# Intelligent_Agriculture_Wifi.net
KiCad netlist of a schematic drawn in Altium Designer
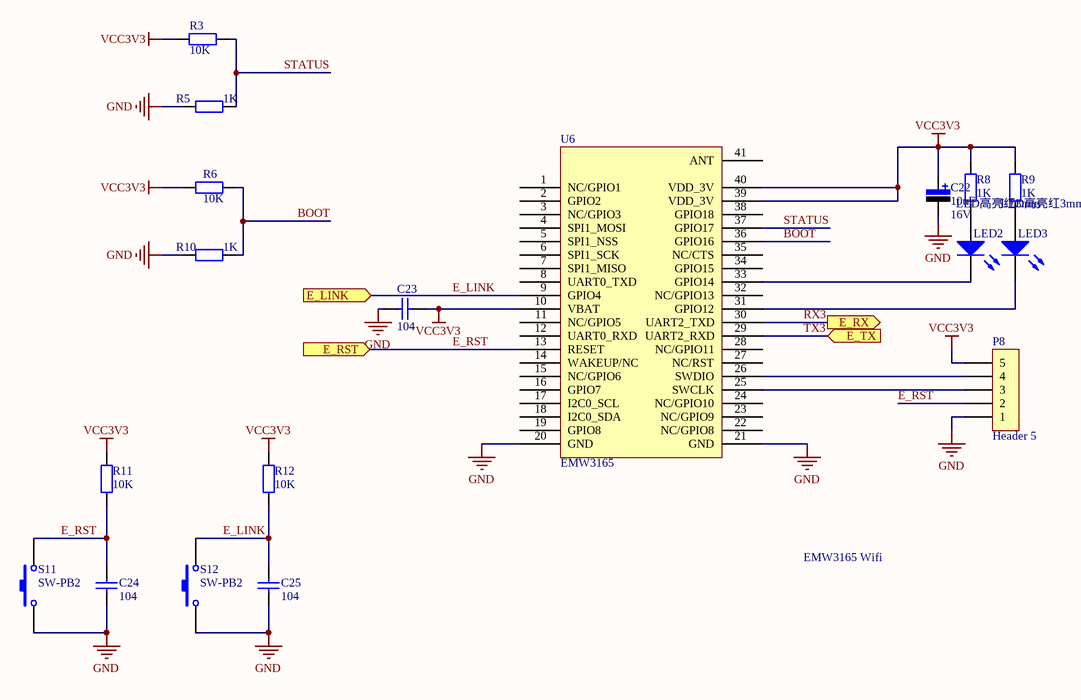
[diagram p0: Intelligent_Agriculture_Wifi.SchDoc]

(export (version "E")
  (design (tool "Eeschema 10.0.6"))
  (components
    (comp (ref "C22")
      (value "10uF")
      (footprint "CAP-3528")
      (description "钽电容")
      (fields
        (field (name "VOL") "16V")
        (field (name "Comment") "Cap Pol")
        (field (name "PUBLISHER") "Altium Limited")
      )
      (libsource (lib "Intelligent_Agriculture_Lib") (part "Cap Pol"))
    )
    (comp (ref "C23")
      (value "104")
      (footprint "C-RAD-0805")
      (description "无极性电容")
      (fields (field (name "Comment") "Cap") (field (name "PUBLISHER") "Altium Limited"))
      (libsource (lib "Intelligent_Agriculture_Lib") (part "Cap"))
    )
    (comp (ref "C24")
      (value "104")
      (footprint "C-RAD-0805")
      (description "无极性电容")
      (fields (field (name "Comment") "Cap") (field (name "PUBLISHER") "Altium Limited"))
      (libsource (lib "Intelligent_Agriculture_Lib") (part "Cap"))
    )
    (comp (ref "C25")
      (value "104")
      (footprint "C-RAD-0805")
      (description "无极性电容")
      (fields (field (name "Comment") "Cap") (field (name "PUBLISHER") "Altium Limited"))
      (libsource (lib "Intelligent_Agriculture_Lib") (part "Cap"))
    )
    (comp (ref "LED2")
      (value "LED0")
      (footprint "LED_A2")
      (description "发光二极管")
      (fields (field (name "PUBLISHER") "Altium Limited"))
      (libsource (lib "Intelligent_Agriculture_Lib") (part "LED0"))
    )
    (comp (ref "LED3")
      (value "LED0")
      (footprint "LED_A2")
      (description "发光二极管")
      (fields (field (name "PUBLISHER") "Altium Limited"))
      (libsource (lib "Intelligent_Agriculture_Lib") (part "LED0"))
    )
    (comp (ref "P8")
      (value "Header 5")
      (footprint "HDR5_A1")
      (description "接插件")
      (fields (field (name "PUBLISHER") "Altium Limited"))
      (libsource (lib "fszhang") (part "Header 5"))
    )
    (comp (ref "R3")
      (value "10K")
      (description "贴片电阻")
      (fields (field (name "Comment") "Res1") (field (name "PUBLISHER") "Altium Limited"))
      (libsource (lib "") (part "Res1_1"))
    )
    (comp (ref "R5")
      (value "1K")
      (description "贴片电阻")
      (fields (field (name "Comment") "Res1") (field (name "PUBLISHER") "Altium Limited"))
      (libsource (lib "") (part "Res1_1"))
    )
    (comp (ref "R6")
      (value "10K")
      (description "贴片电阻")
      (fields (field (name "Comment") "Res1") (field (name "PUBLISHER") "Altium Limited"))
      (libsource (lib "") (part "Res1_1"))
    )
    (comp (ref "R8")
      (value "1K")
      (description "贴片电阻")
      (fields (field (name "Comment") "Res1") (field (name "PUBLISHER") "Altium Limited"))
      (libsource (lib "fszhang") (part "Res1"))
    )
    (comp (ref "R9")
      (value "1K")
      (description "贴片电阻")
      (fields (field (name "Comment") "Res1") (field (name "PUBLISHER") "Altium Limited"))
      (libsource (lib "fszhang") (part "Res1"))
    )
    (comp (ref "R10")
      (value "1K")
      (description "贴片电阻")
      (fields (field (name "Comment") "Res1") (field (name "PUBLISHER") "Altium Limited"))
      (libsource (lib "") (part "Res1_1"))
    )
    (comp (ref "R11")
      (value "10K")
      (description "贴片电阻")
      (fields (field (name "Comment") "Res1") (field (name "PUBLISHER") "Altium Limited"))
      (libsource (lib "") (part "Res1_2"))
    )
    (comp (ref "R12")
      (value "10K")
      (description "贴片电阻")
      (fields (field (name "Comment") "Res1") (field (name "PUBLISHER") "Altium Limited"))
      (libsource (lib "fszhang") (part "Res1"))
    )
    (comp (ref "S11")
      (value "SW-PB2")
      (footprint "SW_PB2-S-3*6*2.5")
      (description "微动开关")
      (fields (field (name "PUBLISHER") "Altium Limited"))
      (libsource (lib "Intelligent_Agriculture_Lib") (part "SW-PB2"))
    )
    (comp (ref "S12")
      (value "SW-PB2")
      (footprint "SW_PB2-S-3*6*2.5")
      (description "微动开关")
      (fields (field (name "PUBLISHER") "Altium Limited"))
      (libsource (lib "Intelligent_Agriculture_Lib") (part "SW-PB2"))
    )
    (comp (ref "U6")
      (value "EMW3165")
      (footprint "EMW3165")
      (description "WIFI 模块")
      (libsource (lib "Intelligent_Agriculture") (part "EMW3165"))
    )
  )
  (nets
    (net (code "1") (name "/BOOT") (class "Default")
      (node (ref "R10") (pin "1") (pinfunction "1_1") (pintype "passive"))
      (node (ref "R6") (pin "1") (pinfunction "1_1") (pintype "passive"))
      (node (ref "U6") (pin "36") (pinfunction "GPIO16_36") (pintype "passive"))
    )
    (net (code "2") (name "/E_LINK") (class "Default")
      (node (ref "C25") (pin "1") (pinfunction "1_1") (pintype "passive"))
      (node (ref "R12") (pin "1") (pinfunction "1_1") (pintype "passive"))
      (node (ref "S12") (pin "2") (pinfunction "2_2") (pintype "passive"))
      (node (ref "U6") (pin "9") (pinfunction "GPIO4_9") (pintype "passive"))
    )
    (net (code "3") (name "/E_RST") (class "Default")
      (node (ref "C24") (pin "1") (pinfunction "1_1") (pintype "passive"))
      (node (ref "P8") (pin "2") (pinfunction "2_2") (pintype "passive"))
      (node (ref "R11") (pin "2") (pinfunction "2_2") (pintype "passive"))
      (node (ref "S11") (pin "2") (pinfunction "2_2") (pintype "passive"))
      (node (ref "U6") (pin "13") (pinfunction "RESET_13") (pintype "passive"))
    )
    (net (code "4") (name "/RX3") (class "Default")
      (node (ref "U6") (pin "30") (pinfunction "UART2_TXD_30") (pintype "passive"))
    )
    (net (code "5") (name "/STATUS") (class "Default")
      (node (ref "R3") (pin "1") (pinfunction "1_1") (pintype "passive"))
      (node (ref "R5") (pin "1") (pinfunction "1_1") (pintype "passive"))
      (node (ref "U6") (pin "37") (pinfunction "GPIO17_37") (pintype "passive"))
    )
    (net (code "6") (name "/TX3") (class "Default")
      (node (ref "U6") (pin "29") (pinfunction "UART2_RXD_29") (pintype "passive"))
    )
    (net (code "7") (name "GND") (class "Default")
      (node (ref "C22") (pin "2") (pinfunction "2_2") (pintype "passive"))
      (node (ref "C23") (pin "1") (pinfunction "1_1") (pintype "passive"))
      (node (ref "C24") (pin "2") (pinfunction "2_2") (pintype "passive"))
      (node (ref "C25") (pin "2") (pinfunction "2_2") (pintype "passive"))
      (node (ref "P8") (pin "1") (pinfunction "1_1") (pintype "passive"))
      (node (ref "R10") (pin "2") (pinfunction "2_2") (pintype "passive"))
      (node (ref "R5") (pin "2") (pinfunction "2_2") (pintype "passive"))
      (node (ref "S11") (pin "1") (pinfunction "1_1") (pintype "passive"))
      (node (ref "S12") (pin "1") (pinfunction "1_1") (pintype "passive"))
      (node (ref "U6") (pin "20") (pinfunction "GND_20") (pintype "passive"))
      (node (ref "U6") (pin "21") (pinfunction "GND_21") (pintype "passive"))
    )
    (net (code "8") (name "Net-(LED2-A)") (class "Default")
      (node (ref "LED2") (pin "1") (pinfunction "A_1") (pintype "passive"))
      (node (ref "R8") (pin "1") (pinfunction "1_1") (pintype "passive"))
    )
    (net (code "9") (name "Net-(LED2-K)") (class "Default")
      (node (ref "LED2") (pin "2") (pinfunction "K_2") (pintype "passive"))
      (node (ref "U6") (pin "33") (pinfunction "GPIO14_33") (pintype "passive"))
    )
    (net (code "10") (name "Net-(LED3-A)") (class "Default")
      (node (ref "LED3") (pin "1") (pinfunction "A_1") (pintype "passive"))
      (node (ref "R9") (pin "1") (pinfunction "1_1") (pintype "passive"))
    )
    (net (code "11") (name "Net-(LED3-K)") (class "Default")
      (node (ref "LED3") (pin "2") (pinfunction "K_2") (pintype "passive"))
      (node (ref "U6") (pin "31") (pinfunction "GPIO12_31") (pintype "passive"))
    )
    (net (code "12") (name "Net-(U6-SWCLK)") (class "Default")
      (node (ref "P8") (pin "3") (pinfunction "3_3") (pintype "passive"))
      (node (ref "U6") (pin "25") (pinfunction "SWCLK_25") (pintype "passive"))
    )
    (net (code "13") (name "Net-(U6-SWDIO)") (class "Default")
      (node (ref "P8") (pin "4") (pinfunction "4_4") (pintype "passive"))
      (node (ref "U6") (pin "26") (pinfunction "SWDIO_26") (pintype "passive"))
    )
    (net (code "14") (name "VCC3V3") (class "Default")
      (node (ref "C22") (pin "1") (pinfunction "1_1") (pintype "passive"))
      (node (ref "C23") (pin "2") (pinfunction "2_2") (pintype "passive"))
      (node (ref "P8") (pin "5") (pinfunction "5_5") (pintype "passive"))
      (node (ref "R11") (pin "1") (pinfunction "1_1") (pintype "passive"))
      (node (ref "R12") (pin "2") (pinfunction "2_2") (pintype "passive"))
      (node (ref "R3") (pin "2") (pinfunction "2_2") (pintype "passive"))
      (node (ref "R6") (pin "2") (pinfunction "2_2") (pintype "passive"))
      (node (ref "R8") (pin "2") (pinfunction "2_2") (pintype "passive"))
      (node (ref "R9") (pin "2") (pinfunction "2_2") (pintype "passive"))
      (node (ref "U6") (pin "10") (pinfunction "VBAT_10") (pintype "passive"))
      (node (ref "U6") (pin "39") (pinfunction "VDD_3V_39") (pintype "passive"))
      (node (ref "U6") (pin "40") (pinfunction "VDD_3V_40") (pintype "passive"))
    )
    (net (code "15") (name "unconnected-(U6-ANT-Pad41)") (class "Default")
      (node (ref "U6") (pin "41") (pinfunction "ANT_41") (pintype "passive"))
    )
    (net (code "16") (name "unconnected-(U6-GPIO2-Pad2)") (class "Default")
      (node (ref "U6") (pin "2") (pinfunction "GPIO2_2") (pintype "passive"))
    )
    (net (code "17") (name "unconnected-(U6-GPIO7-Pad16)") (class "Default")
      (node (ref "U6") (pin "16") (pinfunction "GPIO7_16") (pintype "passive"))
    )
    (net (code "18") (name "unconnected-(U6-GPIO8-Pad19)") (class "Default")
      (node (ref "U6") (pin "19") (pinfunction "GPIO8_19") (pintype "passive"))
    )
    (net (code "19") (name "unconnected-(U6-GPIO15-Pad34)") (class "Default")
      (node (ref "U6") (pin "34") (pinfunction "GPIO15_34") (pintype "passive"))
    )
    (net (code "20") (name "unconnected-(U6-GPIO18-Pad38)") (class "Default")
      (node (ref "U6") (pin "38") (pinfunction "GPIO18_38") (pintype "passive"))
    )
    (net (code "21") (name "unconnected-(U6-I2C0_SCL-Pad17)") (class "Default")
      (node (ref "U6") (pin "17") (pinfunction "I2C0_SCL_17") (pintype "passive"))
    )
    (net (code "22") (name "unconnected-(U6-I2C0_SDA-Pad18)") (class "Default")
      (node (ref "U6") (pin "18") (pinfunction "I2C0_SDA_18") (pintype "passive"))
    )
    (net (code "23") (name "unconnected-(U6-NC{slash}CTS-Pad35)") (class "Default")
      (node (ref "U6") (pin "35") (pinfunction "NC/CTS_35") (pintype "passive"))
    )
    (net (code "24") (name "unconnected-(U6-NC{slash}GPIO1-Pad1)") (class "Default")
      (node (ref "U6") (pin "1") (pinfunction "NC/GPIO1_1") (pintype "passive"))
    )
    (net (code "25") (name "unconnected-(U6-NC{slash}GPIO3-Pad3)") (class "Default")
      (node (ref "U6") (pin "3") (pinfunction "NC/GPIO3_3") (pintype "passive"))
    )
    (net (code "26") (name "unconnected-(U6-NC{slash}GPIO5-Pad11)") (class "Default")
      (node (ref "U6") (pin "11") (pinfunction "NC/GPIO5_11") (pintype "passive"))
    )
    (net (code "27") (name "unconnected-(U6-NC{slash}GPIO6-Pad15)") (class "Default")
      (node (ref "U6") (pin "15") (pinfunction "NC/GPIO6_15") (pintype "passive"))
    )
    (net (code "28") (name "unconnected-(U6-NC{slash}GPIO8-Pad22)") (class "Default")
      (node (ref "U6") (pin "22") (pinfunction "NC/GPIO8_22") (pintype "passive"))
    )
    (net (code "29") (name "unconnected-(U6-NC{slash}GPIO9-Pad23)") (class "Default")
      (node (ref "U6") (pin "23") (pinfunction "NC/GPIO9_23") (pintype "passive"))
    )
    (net (code "30") (name "unconnected-(U6-NC{slash}GPIO10-Pad24)") (class "Default")
      (node (ref "U6") (pin "24") (pinfunction "NC/GPIO10_24") (pintype "passive"))
    )
    (net (code "31") (name "unconnected-(U6-NC{slash}GPIO11-Pad28)") (class "Default")
      (node (ref "U6") (pin "28") (pinfunction "NC/GPIO11_28") (pintype "passive"))
    )
    (net (code "32") (name "unconnected-(U6-NC{slash}GPIO13-Pad32)") (class "Default")
      (node (ref "U6") (pin "32") (pinfunction "NC/GPIO13_32") (pintype "passive"))
    )
    (net (code "33") (name "unconnected-(U6-NC{slash}RST-Pad27)") (class "Default")
      (node (ref "U6") (pin "27") (pinfunction "NC/RST_27") (pintype "passive"))
    )
    (net (code "34") (name "unconnected-(U6-SPI1_MISO-Pad7)") (class "Default")
      (node (ref "U6") (pin "7") (pinfunction "SPI1_MISO_7") (pintype "passive"))
    )
    (net (code "35") (name "unconnected-(U6-SPI1_MOSI-Pad4)") (class "Default")
      (node (ref "U6") (pin "4") (pinfunction "SPI1_MOSI_4") (pintype "passive"))
    )
    (net (code "36") (name "unconnected-(U6-SPI1_NSS-Pad5)") (class "Default")
      (node (ref "U6") (pin "5") (pinfunction "SPI1_NSS_5") (pintype "passive"))
    )
    (net (code "37") (name "unconnected-(U6-SPI1_SCK-Pad6)") (class "Default")
      (node (ref "U6") (pin "6") (pinfunction "SPI1_SCK_6") (pintype "passive"))
    )
    (net (code "38") (name "unconnected-(U6-UART0_RXD-Pad12)") (class "Default")
      (node (ref "U6") (pin "12") (pinfunction "UART0_RXD_12") (pintype "passive"))
    )
    (net (code "39") (name "unconnected-(U6-UART0_TXD-Pad8)") (class "Default")
      (node (ref "U6") (pin "8") (pinfunction "UART0_TXD_8") (pintype "passive"))
    )
    (net (code "40") (name "unconnected-(U6-WAKEUP{slash}NC-Pad14)") (class "Default")
      (node (ref "U6") (pin "14") (pinfunction "WAKEUP/NC_14") (pintype "passive"))
    )
  )
)
